# Stm8_Sheet.net
KiCad netlist of a schematic drawn in Altium Designer
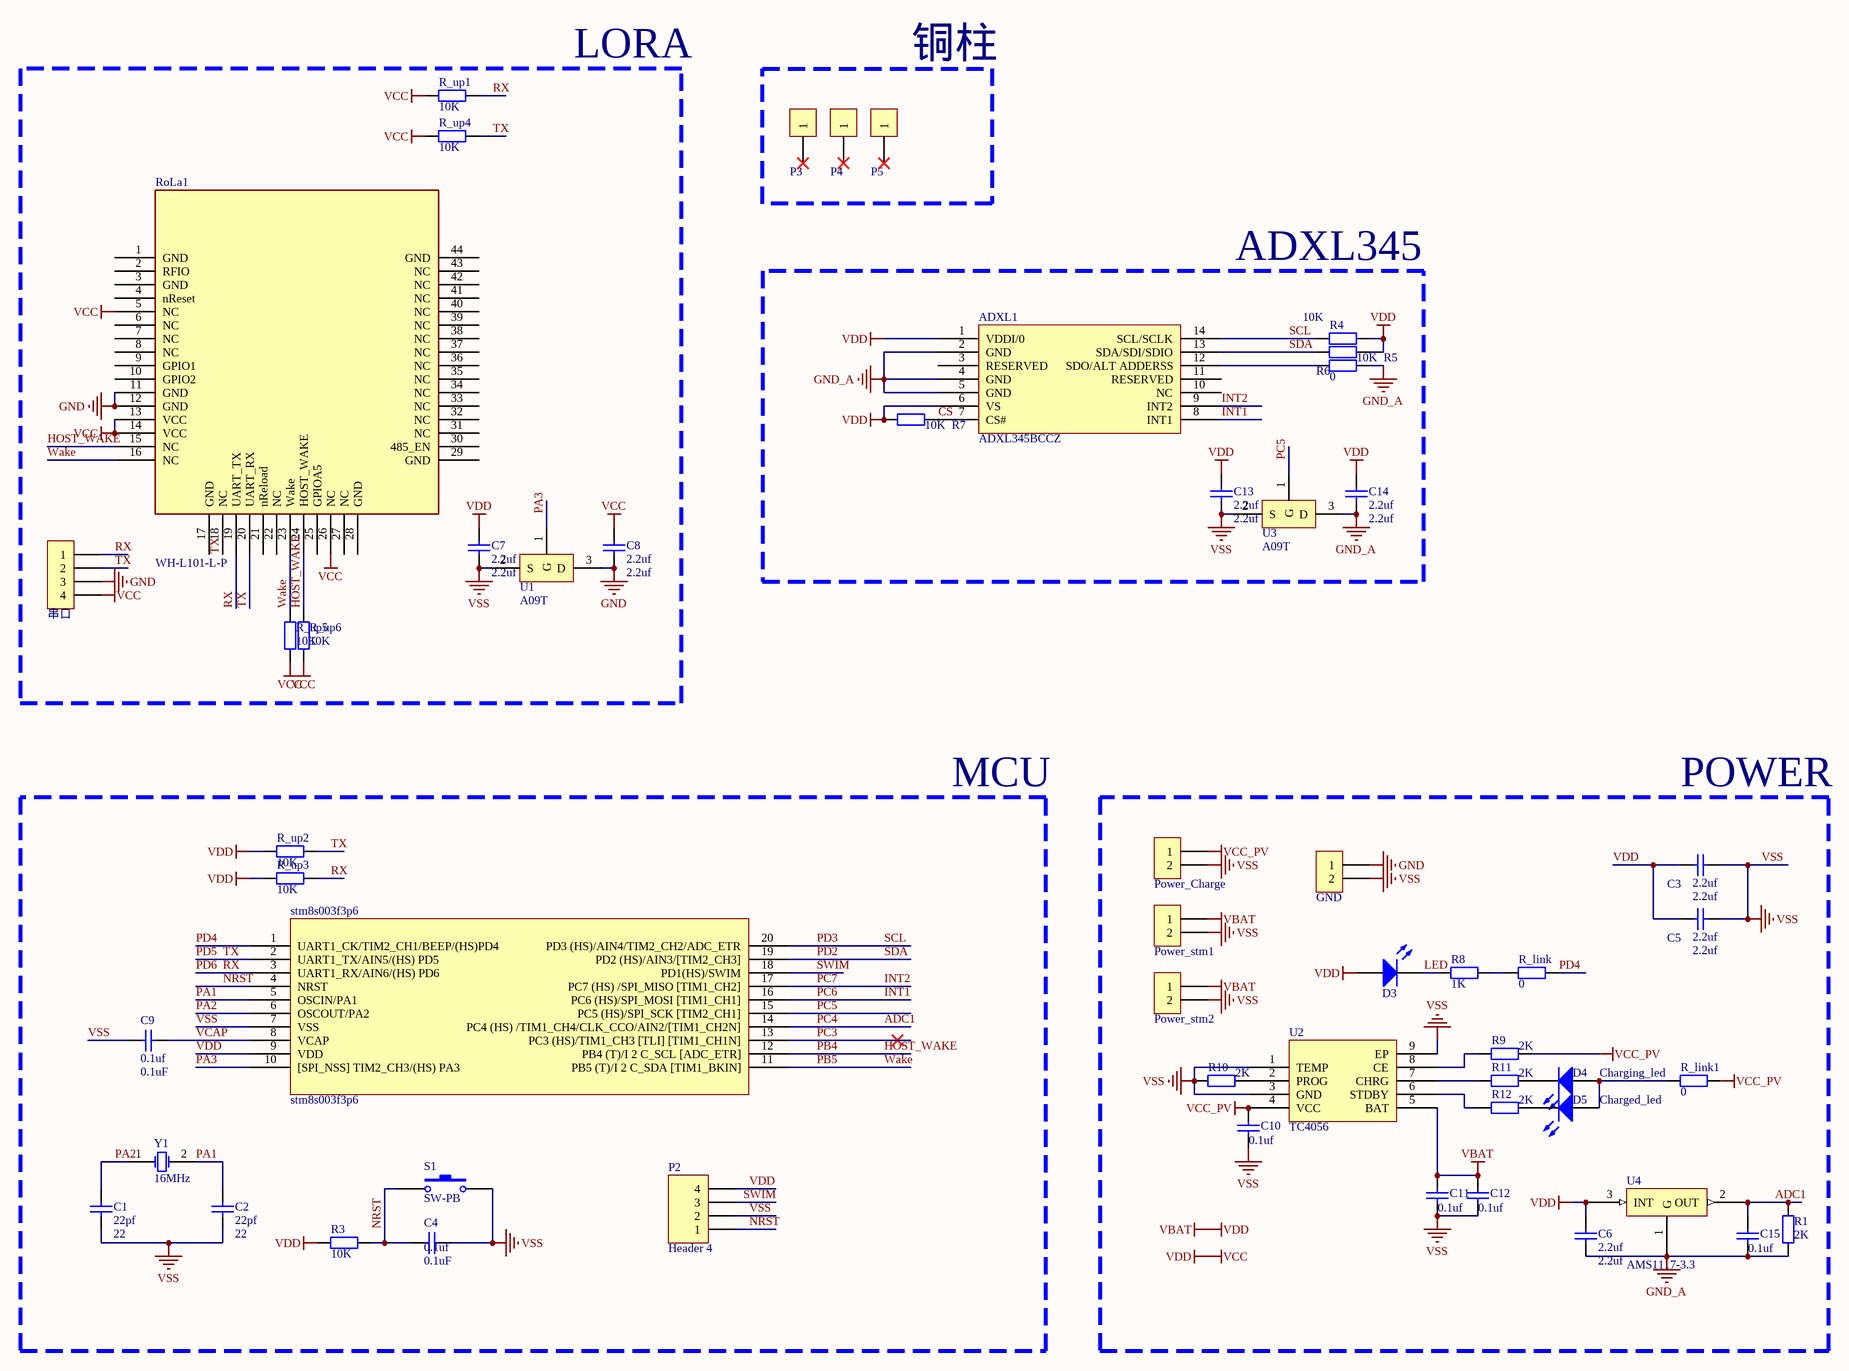
[diagram p0: Stm8_Sheet.SchDoc]

(export (version "E")
  (design (tool "Eeschema 10.0.6"))
  (components
    (comp (ref "ADXL1")
      (value "ADXL345BCCZ")
      (footprint "LGA-14_L5.0-W3.0-P0.80-BL - duplicate")
      (libsource (lib "Stm8_PCB") (part "ADXL345BCCZ"))
    )
    (comp (ref "C1")
      (value "22pf")
      (footprint "Csust_czq6:0603-C")
      (description "Capacitor")
      (fields (field (name "ALTIUM_VALUE") "22") (field (name "PUBLISHER") "Altium Limited"))
      (libsource (lib "PCB_Project") (part "Cap"))
    )
    (comp (ref "C2")
      (value "22pf")
      (footprint "Csust_czq6:0603-C")
      (description "Capacitor")
      (fields (field (name "ALTIUM_VALUE") "22") (field (name "PUBLISHER") "Altium Limited"))
      (libsource (lib "PCB_Project") (part "Cap"))
    )
    (comp (ref "C3")
      (value "2.2uf")
      (footprint "Csust_czq6:0603-C")
      (description "Capacitor")
      (fields (field (name "ALTIUM_VALUE") "2.2uf") (field (name "PUBLISHER") "Altium Limited"))
      (libsource (lib "PCB_Project") (part "Cap"))
    )
    (comp (ref "C4")
      (value "0.1uf")
      (footprint "Csust_czq6:0603-C")
      (description "Capacitor")
      (fields (field (name "ALTIUM_VALUE") "0.1uF") (field (name "PUBLISHER") "Altium Limited"))
      (libsource (lib "Miscellaneous Devices") (part "Cap"))
    )
    (comp (ref "C5")
      (value "2.2uf")
      (footprint "Csust_czq6:0603-C")
      (description "Capacitor")
      (fields (field (name "ALTIUM_VALUE") "2.2uf") (field (name "PUBLISHER") "Altium Limited"))
      (libsource (lib "PCB_Project") (part "Cap"))
    )
    (comp (ref "C6")
      (value "2.2uf")
      (footprint "Csust_czq6:0603-C")
      (description "Capacitor")
      (fields (field (name "ALTIUM_VALUE") "2.2uf") (field (name "PUBLISHER") "Altium Limited"))
      (libsource (lib "PCB_Project") (part "Cap"))
    )
    (comp (ref "C7")
      (value "2.2uf")
      (footprint "Csust_czq6:0603-C")
      (description "Capacitor")
      (fields (field (name "ALTIUM_VALUE") "2.2uf") (field (name "PUBLISHER") "Altium Limited"))
      (libsource (lib "PCB_Project") (part "Cap"))
    )
    (comp (ref "C8")
      (value "2.2uf")
      (footprint "Csust_czq6:0603-C")
      (description "Capacitor")
      (fields (field (name "ALTIUM_VALUE") "2.2uf") (field (name "PUBLISHER") "Altium Limited"))
      (libsource (lib "PCB_Project") (part "Cap"))
    )
    (comp (ref "C9")
      (value "0.1uf")
      (footprint "Csust_czq6:0603-C")
      (description "Capacitor")
      (fields (field (name "ALTIUM_VALUE") "0.1uF") (field (name "PUBLISHER") "Altium Limited"))
      (libsource (lib "Miscellaneous Devices") (part "Cap"))
    )
    (comp (ref "C10")
      (value "0.1uf")
      (footprint "Csust_czq6:0603-C")
      (description "Capacitor")
      (fields (field (name "Comment") "2.2uf") (field (name "PUBLISHER") "Altium Limited"))
      (libsource (lib "PCB_Project") (part "Cap"))
    )
    (comp (ref "C11")
      (value "0.1uf")
      (footprint "Csust_czq6:0603-C")
      (description "Capacitor")
      (fields (field (name "Comment") "2.2uf") (field (name "PUBLISHER") "Altium Limited"))
      (libsource (lib "PCB_Project") (part "Cap"))
    )
    (comp (ref "C12")
      (value "0.1uf")
      (footprint "Csust_czq6:0603-C")
      (description "Capacitor")
      (fields (field (name "Comment") "2.2uf") (field (name "PUBLISHER") "Altium Limited"))
      (libsource (lib "PCB_Project") (part "Cap"))
    )
    (comp (ref "C13")
      (value "2.2uf")
      (footprint "Csust_czq6:0603-C")
      (description "Capacitor")
      (fields (field (name "ALTIUM_VALUE") "2.2uf") (field (name "PUBLISHER") "Altium Limited"))
      (libsource (lib "PCB_Project") (part "Cap"))
    )
    (comp (ref "C14")
      (value "2.2uf")
      (footprint "Csust_czq6:0603-C")
      (description "Capacitor")
      (fields (field (name "ALTIUM_VALUE") "2.2uf") (field (name "PUBLISHER") "Altium Limited"))
      (libsource (lib "PCB_Project") (part "Cap"))
    )
    (comp (ref "C15")
      (value "0.1uf")
      (footprint "Csust_czq6:0603-C")
      (description "Capacitor")
      (fields (field (name "Comment") "2.2uf") (field (name "PUBLISHER") "Altium Limited"))
      (libsource (lib "PCB_Project") (part "Cap"))
    )
    (comp (ref "D3")
      (value "LED0")
      (footprint "Csust_czq6:LED-BLUE-0805")
      (description "发光二极管")
      (fields (field (name "PUBLISHER") "Altium Limited"))
      (libsource (lib "Fszhang") (part "LED0"))
    )
    (comp (ref "D4")
      (value "LED0")
      (footprint "Csust_czq6:LED-BLUE-0805")
      (description "发光二极管")
      (fields (field (name "PUBLISHER") "Altium Limited"))
      (libsource (lib "Fszhang") (part "LED0"))
    )
    (comp (ref "D5")
      (value "LED0")
      (footprint "Csust_czq6:LED-BLUE-0805")
      (description "发光二极管")
      (fields (field (name "PUBLISHER") "Altium Limited"))
      (libsource (lib "Fszhang") (part "LED0"))
    )
    (comp (ref "GND")
      (value "XH接线座-2P")
      (footprint "HDR1X2")
      (libsource (lib "Csust_czq6") (part "XH接线座-2P"))
    )
    (comp (ref "P2")
      (value "Header 4")
      (footprint "HDR1X4")
      (description "Header, 4-Pin")
      (fields (field (name "PUBLISHER") "Altium Limited"))
      (libsource (lib "Miscellaneous Connectors") (part "Header 4"))
    )
    (comp (ref "P3") (value "铜柱孔") (footprint "铜柱孔") (libsource (lib "Csust_czq6") (part "铜柱孔")))
    (comp (ref "P4") (value "铜柱孔") (footprint "铜柱孔") (libsource (lib "Csust_czq6") (part "铜柱孔")))
    (comp (ref "P5") (value "铜柱孔") (footprint "铜柱孔") (libsource (lib "Csust_czq6") (part "铜柱孔")))
    (comp (ref "Power_Charge")
      (value "XH接线座-2P")
      (footprint "XH-2P")
      (libsource (lib "Csust_czq6") (part "XH接线座-2P"))
    )
    (comp (ref "Power_stm1")
      (value "XH接线座-2P")
      (footprint "XH-2P")
      (libsource (lib "Csust_czq6") (part "XH接线座-2P"))
    )
    (comp (ref "Power_stm2")
      (value "XH接线座-2P")
      (footprint "XH-2P")
      (libsource (lib "Csust_czq6") (part "XH接线座-2P"))
    )
    (comp (ref "R1")
      (value "2K")
      (footprint "Csust_czq6:0603-R")
      (description "贴片电阻")
      (fields (field (name "Comment") "1K") (field (name "PUBLISHER") "Altium Limited"))
      (libsource (lib "") (part "Res1_1"))
    )
    (comp (ref "R3")
      (value "10K")
      (footprint "Csust_czq6:0603-R")
      (description "贴片电阻")
      (fields (field (name "PUBLISHER") "Altium Limited"))
      (libsource (lib "Fszhang") (part "Res1"))
    )
    (comp (ref "R4")
      (value "10K")
      (footprint "Csust_czq6:0603-R")
      (description "贴片电阻")
      (fields (field (name "PUBLISHER") "Altium Limited"))
      (libsource (lib "Fszhang") (part "Res1"))
    )
    (comp (ref "R5")
      (value "10K")
      (footprint "Csust_czq6:0603-R")
      (description "贴片电阻")
      (fields (field (name "PUBLISHER") "Altium Limited"))
      (libsource (lib "Fszhang") (part "Res1"))
    )
    (comp (ref "R6")
      (value "0")
      (footprint "Csust_czq6:0603-R")
      (description "贴片电阻")
      (fields (field (name "PUBLISHER") "Altium Limited"))
      (libsource (lib "Fszhang") (part "Res1"))
    )
    (comp (ref "R7")
      (value "10K")
      (footprint "Csust_czq6:0603-R")
      (description "贴片电阻")
      (fields (field (name "PUBLISHER") "Altium Limited"))
      (libsource (lib "Fszhang") (part "Res1"))
    )
    (comp (ref "R8")
      (value "1K")
      (footprint "Csust_czq6:0603-R")
      (description "贴片电阻")
      (fields (field (name "PUBLISHER") "Altium Limited"))
      (libsource (lib "Fszhang") (part "Res1"))
    )
    (comp (ref "R9")
      (value "2K")
      (footprint "Csust_czq6:0603-R")
      (description "贴片电阻")
      (fields (field (name "Comment") "1K") (field (name "PUBLISHER") "Altium Limited"))
      (libsource (lib "Fszhang") (part "Res1"))
    )
    (comp (ref "R10")
      (value "2K")
      (footprint "Csust_czq6:0603-R")
      (description "贴片电阻")
      (fields (field (name "Comment") "1K") (field (name "PUBLISHER") "Altium Limited"))
      (libsource (lib "Fszhang") (part "Res1"))
    )
    (comp (ref "R11")
      (value "2K")
      (footprint "Csust_czq6:0603-R")
      (description "贴片电阻")
      (fields (field (name "Comment") "1K") (field (name "PUBLISHER") "Altium Limited"))
      (libsource (lib "Fszhang") (part "Res1"))
    )
    (comp (ref "R12")
      (value "2K")
      (footprint "Csust_czq6:0603-R")
      (description "贴片电阻")
      (fields (field (name "Comment") "1K") (field (name "PUBLISHER") "Altium Limited"))
      (libsource (lib "Fszhang") (part "Res1"))
    )
    (comp (ref "RoLa1")
      (value "WH-L101-L-P")
      (footprint "WH-L101-L-P")
      (libsource (lib "steven") (part "WH-L101-L-P"))
    )
    (comp (ref "R_link")
      (value "0")
      (footprint "0402")
      (description "贴片电阻")
      (fields (field (name "Comment") "1K") (field (name "PUBLISHER") "Altium Limited"))
      (libsource (lib "Fszhang") (part "Res1"))
    )
    (comp (ref "R_link1")
      (value "0")
      (footprint "0402")
      (description "贴片电阻")
      (fields (field (name "Comment") "1K") (field (name "PUBLISHER") "Altium Limited"))
      (libsource (lib "Fszhang") (part "Res1"))
    )
    (comp (ref "R_up1")
      (value "10K")
      (footprint "Csust_czq6:0603-R")
      (description "贴片电阻")
      (fields (field (name "PUBLISHER") "Altium Limited"))
      (libsource (lib "Fszhang") (part "Res1"))
    )
    (comp (ref "R_up2")
      (value "10K")
      (footprint "Csust_czq6:0603-R")
      (description "贴片电阻")
      (fields (field (name "PUBLISHER") "Altium Limited"))
      (libsource (lib "Fszhang") (part "Res1"))
    )
    (comp (ref "R_up3")
      (value "10K")
      (footprint "Csust_czq6:0603-R")
      (description "贴片电阻")
      (fields (field (name "PUBLISHER") "Altium Limited"))
      (libsource (lib "Fszhang") (part "Res1"))
    )
    (comp (ref "R_up4")
      (value "10K")
      (footprint "Csust_czq6:0603-R")
      (description "贴片电阻")
      (fields (field (name "PUBLISHER") "Altium Limited"))
      (libsource (lib "Fszhang") (part "Res1"))
    )
    (comp (ref "R_up5")
      (value "10K")
      (footprint "Csust_czq6:0603-R")
      (description "贴片电阻")
      (fields (field (name "PUBLISHER") "Altium Limited"))
      (libsource (lib "") (part "Res1_1"))
    )
    (comp (ref "R_up6")
      (value "10K")
      (footprint "Csust_czq6:0603-R")
      (description "贴片电阻")
      (fields (field (name "PUBLISHER") "Altium Limited"))
      (libsource (lib "") (part "Res1_1"))
    )
    (comp (ref "S1")
      (value "SW-PB")
      (footprint "Csust_czq6:按键(贴片)")
      (description "微动开关")
      (fields (field (name "PUBLISHER") "Altium Limited"))
      (libsource (lib "Fszhang") (part "SW-PB"))
    )
    (comp (ref "stm8s003f3p6")
      (value "stm8s003f3p6")
      (footprint "TSSOP20")
      (libsource (lib "steven") (part "stm8s003f3p6"))
    )
    (comp (ref "U1") (value "A09T") (footprint "SOT23") (libsource (lib "steven") (part "A09T")))
    (comp (ref "U2")
      (value "TC4056")
      (footprint "SOP-8_L4.9-W3.9-P1.27-LS6.0-BL-EP")
      (description "TC4056电源模块")
      (libsource (lib "steven") (part "TC4056"))
    )
    (comp (ref "U3") (value "A09T") (footprint "SOT23") (libsource (lib "steven") (part "A09T")))
    (comp (ref "U4")
      (value "AMS1117-3.3")
      (footprint "SOT-223")
      (libsource (lib "steven") (part "AMS1117-3.3"))
    )
    (comp (ref "Y1")
      (value "16MHz")
      (footprint "OSC-SMD_L5.0-W3.2 - duplicate")
      (description "Crystal Oscillator")
      (fields (field (name "PUBLISHER") "Altium Limited"))
      (libsource (lib "steven") (part "XTAL_1"))
    )
    (comp (ref "串口") (value "XH接线座-4P") (footprint "HDR1X4") (libsource (lib "Csust_czq6") (part "XH接线座-4P")))
  )
  (nets
    (net (code "1") (name "/ADC1") (class "Default")
      (node (ref "C15") (pin "1") (pinfunction "1_1") (pintype "passive"))
      (node (ref "R1") (pin "1") (pinfunction "1_1") (pintype "passive"))
      (node (ref "U4") (pin "2") (pinfunction "OUT_2") (pintype "output"))
      (node (ref "stm8s003f3p6") (pin "14") (pinfunction "PC4_(HS)_/TIM1_CH4/CLK_CCO/AIN2/[TIM1_CH2N]_14") (pintype "passive"))
    )
    (net (code "2") (name "/CS") (class "Default")
      (node (ref "ADXL1") (pin "7") (pinfunction "CS#_7") (pintype "passive"))
      (node (ref "R7") (pin "1") (pinfunction "1_1") (pintype "passive"))
    )
    (net (code "3") (name "/HOST_WAKE") (class "Default")
      (node (ref "R_up6") (pin "1") (pinfunction "1_1") (pintype "passive"))
      (node (ref "RoLa1") (pin "15") (pinfunction "NC_15") (pintype "passive"))
      (node (ref "RoLa1") (pin "24") (pinfunction "HOST_WAKE_24") (pintype "passive"))
      (node (ref "stm8s003f3p6") (pin "12") (pinfunction "PB4_(T)/I_2_C_SCL_[ADC_ETR]_12") (pintype "passive"))
    )
    (net (code "4") (name "/INT1") (class "Default")
      (node (ref "ADXL1") (pin "8") (pinfunction "INT1_8") (pintype "passive"))
      (node (ref "stm8s003f3p6") (pin "16") (pinfunction "PC6_(HS)/SPI_MOSI_[TIM1_CH1]_16") (pintype "passive"))
    )
    (net (code "5") (name "/INT2") (class "Default")
      (node (ref "ADXL1") (pin "9") (pinfunction "INT2_9") (pintype "passive"))
      (node (ref "stm8s003f3p6") (pin "17") (pinfunction "PC7_(HS)_/SPI_MISO_[TIM1_CH2]_17") (pintype "passive"))
    )
    (net (code "6") (name "/LED") (class "Default")
      (node (ref "D3") (pin "2") (pinfunction "K_2") (pintype "passive"))
      (node (ref "R8") (pin "2") (pinfunction "2_2") (pintype "passive"))
    )
    (net (code "7") (name "/NRST") (class "Default")
      (node (ref "C4") (pin "2") (pinfunction "2_2") (pintype "passive"))
      (node (ref "P2") (pin "1") (pinfunction "1_1") (pintype "passive"))
      (node (ref "R3") (pin "1") (pinfunction "1_1") (pintype "passive"))
      (node (ref "S1") (pin "1") (pinfunction "1_1") (pintype "passive"))
      (node (ref "stm8s003f3p6") (pin "4") (pinfunction "NRST_4") (pintype "passive"))
    )
    (net (code "8") (name "/PA1") (class "Default")
      (node (ref "C2") (pin "2") (pinfunction "2_2") (pintype "passive"))
      (node (ref "Y1") (pin "2") (pinfunction "OSC2_2") (pintype "passive"))
      (node (ref "stm8s003f3p6") (pin "5") (pinfunction "OSCIN/PA1_5") (pintype "passive"))
    )
    (net (code "9") (name "/PA2") (class "Default")
      (node (ref "C1") (pin "2") (pinfunction "2_2") (pintype "passive"))
      (node (ref "Y1") (pin "1") (pinfunction "OSC1_1") (pintype "passive"))
      (node (ref "stm8s003f3p6") (pin "6") (pinfunction "OSCOUT/PA2_6") (pintype "passive"))
    )
    (net (code "10") (name "/PA3") (class "Default")
      (node (ref "U1") (pin "1") (pinfunction "G_1") (pintype "passive"))
      (node (ref "stm8s003f3p6") (pin "10") (pinfunction "[SPI_NSS]_TIM2_CH3/(HS)_PA3_10") (pintype "passive"))
    )
    (net (code "11") (name "/PB5") (class "Default")
      (node (ref "R_up5") (pin "1") (pinfunction "1_1") (pintype "passive"))
      (node (ref "RoLa1") (pin "16") (pinfunction "NC_16") (pintype "passive"))
      (node (ref "RoLa1") (pin "23") (pinfunction "Wake_23") (pintype "passive"))
      (node (ref "stm8s003f3p6") (pin "11") (pinfunction "PB5_(T)/I_2_C_SDA_[TIM1_BKIN]_11") (pintype "passive"))
    )
    (net (code "12") (name "/PC3") (class "Default")
      (node (ref "stm8s003f3p6") (pin "13") (pinfunction "PC3_(HS)/TIM1_CH3_[TLI]_[TIM1_CH1N]_13") (pintype "passive"))
    )
    (net (code "13") (name "/PC5") (class "Default")
      (node (ref "U3") (pin "1") (pinfunction "G_1") (pintype "passive"))
      (node (ref "stm8s003f3p6") (pin "15") (pinfunction "PC5_(HS)/SPI_SCK_[TIM2_CH1]_15") (pintype "passive"))
    )
    (net (code "14") (name "/PD2") (class "Default")
      (node (ref "ADXL1") (pin "13") (pinfunction "SDA/SDI/SDIO_13") (pintype "passive"))
      (node (ref "R5") (pin "2") (pinfunction "2_2") (pintype "passive"))
      (node (ref "stm8s003f3p6") (pin "19") (pinfunction "PD2_(HS)/AIN3/[TIM2_CH3]_19") (pintype "passive"))
    )
    (net (code "15") (name "/PD3") (class "Default")
      (node (ref "ADXL1") (pin "14") (pinfunction "SCL/SCLK_14") (pintype "passive"))
      (node (ref "R4") (pin "2") (pinfunction "2_2") (pintype "passive"))
      (node (ref "stm8s003f3p6") (pin "20") (pinfunction "PD3_(HS)/AIN4/TIM2_CH2/ADC_ETR_20") (pintype "passive"))
    )
    (net (code "16") (name "/PD4") (class "Default")
      (node (ref "R_link") (pin "1") (pinfunction "1_1") (pintype "passive"))
      (node (ref "stm8s003f3p6") (pin "1") (pinfunction "UART1_CK/TIM2_CH1/BEEP/(HS)PD4_1") (pintype "passive"))
    )
    (net (code "17") (name "/PD5") (class "Default")
      (node (ref "R_up2") (pin "1") (pinfunction "1_1") (pintype "passive"))
      (node (ref "R_up4") (pin "1") (pinfunction "1_1") (pintype "passive"))
      (node (ref "RoLa1") (pin "18") (pinfunction "NC_18") (pintype "passive"))
      (node (ref "RoLa1") (pin "20") (pinfunction "UART_RX_20") (pintype "passive"))
      (node (ref "stm8s003f3p6") (pin "2") (pinfunction "UART1_TX/AIN5/(HS)_PD5_2") (pintype "passive"))
      (node (ref "串口") (pin "2") (pinfunction "2_2") (pintype "passive"))
    )
    (net (code "18") (name "/PD6") (class "Default")
      (node (ref "R_up1") (pin "1") (pinfunction "1_1") (pintype "passive"))
      (node (ref "R_up3") (pin "1") (pinfunction "1_1") (pintype "passive"))
      (node (ref "RoLa1") (pin "19") (pinfunction "UART_TX_19") (pintype "passive"))
      (node (ref "stm8s003f3p6") (pin "3") (pinfunction "UART1_RX/AIN6/(HS)_PD6_3") (pintype "passive"))
      (node (ref "串口") (pin "1") (pinfunction "1_1") (pintype "passive"))
    )
    (net (code "19") (name "/SWIM") (class "Default")
      (node (ref "P2") (pin "3") (pinfunction "3_3") (pintype "passive"))
      (node (ref "stm8s003f3p6") (pin "18") (pinfunction "PD1(HS)/SWIM_18") (pintype "passive"))
    )
    (net (code "20") (name "/VCAP") (class "Default")
      (node (ref "C9") (pin "1") (pinfunction "1_1") (pintype "passive"))
      (node (ref "stm8s003f3p6") (pin "8") (pinfunction "VCAP_8") (pintype "passive"))
    )
    (net (code "21") (name "GND") (class "Default")
      (node (ref "C8") (pin "2") (pinfunction "2_2") (pintype "passive"))
      (node (ref "GND") (pin "1") (pinfunction "1_1") (pintype "passive"))
      (node (ref "RoLa1") (pin "11") (pinfunction "GND_11") (pintype "passive"))
      (node (ref "RoLa1") (pin "12") (pinfunction "GND_12") (pintype "passive"))
      (node (ref "U1") (pin "3") (pinfunction "D_3") (pintype "passive"))
      (node (ref "串口") (pin "3") (pinfunction "3_3") (pintype "passive"))
    )
    (net (code "22") (name "GND_A") (class "Default")
      (node (ref "ADXL1") (pin "2") (pinfunction "GND_2") (pintype "passive"))
      (node (ref "ADXL1") (pin "4") (pinfunction "GND_4") (pintype "passive"))
      (node (ref "ADXL1") (pin "5") (pinfunction "GND_5") (pintype "passive"))
      (node (ref "C14") (pin "2") (pinfunction "2_2") (pintype "passive"))
      (node (ref "C15") (pin "2") (pinfunction "2_2") (pintype "passive"))
      (node (ref "C6") (pin "2") (pinfunction "2_2") (pintype "passive"))
      (node (ref "R1") (pin "2") (pinfunction "2_2") (pintype "passive"))
      (node (ref "R6") (pin "1") (pinfunction "1_1") (pintype "passive"))
      (node (ref "U3") (pin "3") (pinfunction "D_3") (pintype "passive"))
      (node (ref "U4") (pin "1") (pinfunction "G_1") (pintype "passive"))
    )
    (net (code "23") (name "Net-(ADXL1-SDO{slash}ALT_ADDERSS)") (class "Default")
      (node (ref "ADXL1") (pin "12") (pinfunction "SDO/ALT_ADDERSS_12") (pintype "passive"))
      (node (ref "R6") (pin "2") (pinfunction "2_2") (pintype "passive"))
    )
    (net (code "24") (name "Net-(D4-A)") (class "Default")
      (node (ref "D4") (pin "1") (pinfunction "A_1") (pintype "passive"))
      (node (ref "D5") (pin "1") (pinfunction "A_1") (pintype "passive"))
      (node (ref "R_link1") (pin "2") (pinfunction "2_2") (pintype "passive"))
    )
    (net (code "25") (name "Net-(D4-K)") (class "Default")
      (node (ref "D4") (pin "2") (pinfunction "K_2") (pintype "passive"))
      (node (ref "R11") (pin "1") (pinfunction "1_1") (pintype "passive"))
    )
    (net (code "26") (name "Net-(D5-K)") (class "Default")
      (node (ref "D5") (pin "2") (pinfunction "K_2") (pintype "passive"))
      (node (ref "R12") (pin "1") (pinfunction "1_1") (pintype "passive"))
    )
    (net (code "27") (name "Net-(R8-Pad1)") (class "Default")
      (node (ref "R8") (pin "1") (pinfunction "1_1") (pintype "passive"))
      (node (ref "R_link") (pin "2") (pinfunction "2_2") (pintype "passive"))
    )
    (net (code "28") (name "Net-(U2-CE)") (class "Default")
      (node (ref "R9") (pin "2") (pinfunction "2_2") (pintype "passive"))
      (node (ref "U2") (pin "8") (pinfunction "CE_8") (pintype "passive"))
    )
    (net (code "29") (name "Net-(U2-CHRG)") (class "Default")
      (node (ref "R11") (pin "2") (pinfunction "2_2") (pintype "passive"))
      (node (ref "U2") (pin "7") (pinfunction "CHRG_7") (pintype "passive"))
    )
    (net (code "30") (name "Net-(U2-PROG)") (class "Default")
      (node (ref "R10") (pin "1") (pinfunction "1_1") (pintype "passive"))
      (node (ref "U2") (pin "2") (pinfunction "PROG_2") (pintype "passive"))
    )
    (net (code "31") (name "Net-(U2-STDBY)") (class "Default")
      (node (ref "R12") (pin "2") (pinfunction "2_2") (pintype "passive"))
      (node (ref "U2") (pin "6") (pinfunction "STDBY_6") (pintype "passive"))
    )
    (net (code "32") (name "VBAT") (class "Default")
      (node (ref "ADXL1") (pin "1") (pinfunction "VDDI/0_1") (pintype "passive"))
      (node (ref "ADXL1") (pin "6") (pinfunction "VS_6") (pintype "passive"))
      (node (ref "C11") (pin "1") (pinfunction "1_1") (pintype "passive"))
      (node (ref "C12") (pin "1") (pinfunction "1_1") (pintype "passive"))
      (node (ref "C13") (pin "1") (pinfunction "1_1") (pintype "passive"))
      (node (ref "C14") (pin "1") (pinfunction "1_1") (pintype "passive"))
      (node (ref "C3") (pin "2") (pinfunction "2_2") (pintype "passive"))
      (node (ref "C5") (pin "2") (pinfunction "2_2") (pintype "passive"))
      (node (ref "C6") (pin "1") (pinfunction "1_1") (pintype "passive"))
      (node (ref "C7") (pin "1") (pinfunction "1_1") (pintype "passive"))
      (node (ref "C8") (pin "1") (pinfunction "1_1") (pintype "passive"))
      (node (ref "D3") (pin "1") (pinfunction "A_1") (pintype "passive"))
      (node (ref "P2") (pin "4") (pinfunction "4_4") (pintype "passive"))
      (node (ref "Power_stm1") (pin "1") (pinfunction "1_1") (pintype "passive"))
      (node (ref "Power_stm2") (pin "1") (pinfunction "1_1") (pintype "passive"))
      (node (ref "R3") (pin "2") (pinfunction "2_2") (pintype "passive"))
      (node (ref "R4") (pin "1") (pinfunction "1_1") (pintype "passive"))
      (node (ref "R5") (pin "1") (pinfunction "1_1") (pintype "passive"))
      (node (ref "R7") (pin "2") (pinfunction "2_2") (pintype "passive"))
      (node (ref "R_up1") (pin "2") (pinfunction "2_2") (pintype "passive"))
      (node (ref "R_up2") (pin "2") (pinfunction "2_2") (pintype "passive"))
      (node (ref "R_up3") (pin "2") (pinfunction "2_2") (pintype "passive"))
      (node (ref "R_up4") (pin "2") (pinfunction "2_2") (pintype "passive"))
      (node (ref "R_up5") (pin "2") (pinfunction "2_2") (pintype "passive"))
      (node (ref "R_up6") (pin "2") (pinfunction "2_2") (pintype "passive"))
      (node (ref "RoLa1") (pin "13") (pinfunction "VCC_13") (pintype "passive"))
      (node (ref "RoLa1") (pin "14") (pinfunction "VCC_14") (pintype "passive"))
      (node (ref "RoLa1") (pin "26") (pinfunction "NC_26") (pintype "passive"))
      (node (ref "RoLa1") (pin "5") (pinfunction "NC_5") (pintype "passive"))
      (node (ref "U2") (pin "5") (pinfunction "BAT_5") (pintype "passive"))
      (node (ref "U4") (pin "3") (pinfunction "INT_3") (pintype "input"))
      (node (ref "stm8s003f3p6") (pin "9") (pinfunction "VDD_9") (pintype "passive"))
      (node (ref "串口") (pin "4") (pinfunction "4_4") (pintype "passive"))
    )
    (net (code "33") (name "VCC_PV") (class "Default")
      (node (ref "C10") (pin "1") (pinfunction "1_1") (pintype "passive"))
      (node (ref "Power_Charge") (pin "1") (pinfunction "1_1") (pintype "passive"))
      (node (ref "R9") (pin "1") (pinfunction "1_1") (pintype "passive"))
      (node (ref "R_link1") (pin "1") (pinfunction "1_1") (pintype "passive"))
      (node (ref "U2") (pin "4") (pinfunction "VCC_4") (pintype "passive"))
    )
    (net (code "34") (name "VSS") (class "Default")
      (node (ref "C1") (pin "1") (pinfunction "1_1") (pintype "passive"))
      (node (ref "C10") (pin "2") (pinfunction "2_2") (pintype "passive"))
      (node (ref "C11") (pin "2") (pinfunction "2_2") (pintype "passive"))
      (node (ref "C12") (pin "2") (pinfunction "2_2") (pintype "passive"))
      (node (ref "C13") (pin "2") (pinfunction "2_2") (pintype "passive"))
      (node (ref "C2") (pin "1") (pinfunction "1_1") (pintype "passive"))
      (node (ref "C3") (pin "1") (pinfunction "1_1") (pintype "passive"))
      (node (ref "C4") (pin "1") (pinfunction "1_1") (pintype "passive"))
      (node (ref "C5") (pin "1") (pinfunction "1_1") (pintype "passive"))
      (node (ref "C7") (pin "2") (pinfunction "2_2") (pintype "passive"))
      (node (ref "C9") (pin "2") (pinfunction "2_2") (pintype "passive"))
      (node (ref "GND") (pin "2") (pinfunction "2_2") (pintype "passive"))
      (node (ref "P2") (pin "2") (pinfunction "2_2") (pintype "passive"))
      (node (ref "Power_Charge") (pin "2") (pinfunction "2_2") (pintype "passive"))
      (node (ref "Power_stm1") (pin "2") (pinfunction "2_2") (pintype "passive"))
      (node (ref "Power_stm2") (pin "2") (pinfunction "2_2") (pintype "passive"))
      (node (ref "R10") (pin "2") (pinfunction "2_2") (pintype "passive"))
      (node (ref "S1") (pin "2") (pinfunction "2_2") (pintype "passive"))
      (node (ref "U1") (pin "2") (pinfunction "S_2") (pintype "passive"))
      (node (ref "U2") (pin "1") (pinfunction "TEMP_1") (pintype "passive"))
      (node (ref "U2") (pin "3") (pinfunction "GND_3") (pintype "passive"))
      (node (ref "U2") (pin "9") (pinfunction "EP_9") (pintype "passive"))
      (node (ref "U3") (pin "2") (pinfunction "S_2") (pintype "passive"))
      (node (ref "stm8s003f3p6") (pin "7") (pinfunction "VSS_7") (pintype "passive"))
    )
    (net (code "35") (name "unconnected-(ADXL1-NC-Pad10)") (class "Default")
      (node (ref "ADXL1") (pin "10") (pinfunction "NC_10") (pintype "passive"))
    )
    (net (code "36") (name "unconnected-(ADXL1-RESERVED-Pad3)") (class "Default")
      (node (ref "ADXL1") (pin "3") (pinfunction "RESERVED_3") (pintype "passive"))
    )
    (net (code "37") (name "unconnected-(ADXL1-RESERVED-Pad11)") (class "Default")
      (node (ref "ADXL1") (pin "11") (pinfunction "RESERVED_11") (pintype "passive"))
    )
    (net (code "38") (name "unconnected-(P3-Pad1)") (class "Default")
      (node (ref "P3") (pin "1") (pinfunction "1_1") (pintype "passive+no_connect"))
    )
    (net (code "39") (name "unconnected-(P4-Pad1)") (class "Default")
      (node (ref "P4") (pin "1") (pinfunction "1_1") (pintype "passive+no_connect"))
    )
    (net (code "40") (name "unconnected-(P5-Pad1)") (class "Default")
      (node (ref "P5") (pin "1") (pinfunction "1_1") (pintype "passive+no_connect"))
    )
    (net (code "41") (name "unconnected-(RoLa1-485_EN-Pad30)") (class "Default")
      (node (ref "RoLa1") (pin "30") (pinfunction "485_EN_30") (pintype "passive"))
    )
    (net (code "42") (name "unconnected-(RoLa1-GND-Pad1)") (class "Default")
      (node (ref "RoLa1") (pin "1") (pinfunction "GND_1") (pintype "passive"))
    )
    (net (code "43") (name "unconnected-(RoLa1-GND-Pad3)") (class "Default")
      (node (ref "RoLa1") (pin "3") (pinfunction "GND_3") (pintype "passive"))
    )
    (net (code "44") (name "unconnected-(RoLa1-GND-Pad17)") (class "Default")
      (node (ref "RoLa1") (pin "17") (pinfunction "GND_17") (pintype "passive"))
    )
    (net (code "45") (name "unconnected-(RoLa1-GND-Pad28)") (class "Default")
      (node (ref "RoLa1") (pin "28") (pinfunction "GND_28") (pintype "passive"))
    )
    (net (code "46") (name "unconnected-(RoLa1-GND-Pad29)") (class "Default")
      (node (ref "RoLa1") (pin "29") (pinfunction "GND_29") (pintype "passive"))
    )
    (net (code "47") (name "unconnected-(RoLa1-GND-Pad44)") (class "Default")
      (node (ref "RoLa1") (pin "44") (pinfunction "GND_44") (pintype "passive"))
    )
    (net (code "48") (name "unconnected-(RoLa1-GPIO1-Pad9)") (class "Default")
      (node (ref "RoLa1") (pin "9") (pinfunction "GPIO1_9") (pintype "passive"))
    )
    (net (code "49") (name "unconnected-(RoLa1-GPIO2-Pad10)") (class "Default")
      (node (ref "RoLa1") (pin "10") (pinfunction "GPIO2_10") (pintype "passive"))
    )
    (net (code "50") (name "unconnected-(RoLa1-GPIOA5-Pad25)") (class "Default")
      (node (ref "RoLa1") (pin "25") (pinfunction "GPIOA5_25") (pintype "passive"))
    )
    (net (code "51") (name "unconnected-(RoLa1-NC-Pad6)") (class "Default")
      (node (ref "RoLa1") (pin "6") (pinfunction "NC_6") (pintype "passive"))
    )
    (net (code "52") (name "unconnected-(RoLa1-NC-Pad7)") (class "Default")
      (node (ref "RoLa1") (pin "7") (pinfunction "NC_7") (pintype "passive"))
    )
    (net (code "53") (name "unconnected-(RoLa1-NC-Pad8)") (class "Default")
      (node (ref "RoLa1") (pin "8") (pinfunction "NC_8") (pintype "passive"))
    )
    (net (code "54") (name "unconnected-(RoLa1-NC-Pad22)") (class "Default")
      (node (ref "RoLa1") (pin "22") (pinfunction "NC_22") (pintype "passive"))
    )
    (net (code "55") (name "unconnected-(RoLa1-NC-Pad27)") (class "Default")
      (node (ref "RoLa1") (pin "27") (pinfunction "NC_27") (pintype "passive"))
    )
    (net (code "56") (name "unconnected-(RoLa1-NC-Pad31)") (class "Default")
      (node (ref "RoLa1") (pin "31") (pinfunction "NC_31") (pintype "passive"))
    )
    (net (code "57") (name "unconnected-(RoLa1-NC-Pad32)") (class "Default")
      (node (ref "RoLa1") (pin "32") (pinfunction "NC_32") (pintype "passive"))
    )
    (net (code "58") (name "unconnected-(RoLa1-NC-Pad33)") (class "Default")
      (node (ref "RoLa1") (pin "33") (pinfunction "NC_33") (pintype "passive"))
    )
    (net (code "59") (name "unconnected-(RoLa1-NC-Pad34)") (class "Default")
      (node (ref "RoLa1") (pin "34") (pinfunction "NC_34") (pintype "passive"))
    )
    (net (code "60") (name "unconnected-(RoLa1-NC-Pad35)") (class "Default")
      (node (ref "RoLa1") (pin "35") (pinfunction "NC_35") (pintype "passive"))
    )
    (net (code "61") (name "unconnected-(RoLa1-NC-Pad36)") (class "Default")
      (node (ref "RoLa1") (pin "36") (pinfunction "NC_36") (pintype "passive"))
    )
    (net (code "62") (name "unconnected-(RoLa1-NC-Pad37)") (class "Default")
      (node (ref "RoLa1") (pin "37") (pinfunction "NC_37") (pintype "passive"))
    )
    (net (code "63") (name "unconnected-(RoLa1-NC-Pad38)") (class "Default")
      (node (ref "RoLa1") (pin "38") (pinfunction "NC_38") (pintype "passive"))
    )
    (net (code "64") (name "unconnected-(RoLa1-NC-Pad39)") (class "Default")
      (node (ref "RoLa1") (pin "39") (pinfunction "NC_39") (pintype "passive"))
    )
    (net (code "65") (name "unconnected-(RoLa1-NC-Pad40)") (class "Default")
      (node (ref "RoLa1") (pin "40") (pinfunction "NC_40") (pintype "passive"))
    )
    (net (code "66") (name "unconnected-(RoLa1-NC-Pad41)") (class "Default")
      (node (ref "RoLa1") (pin "41") (pinfunction "NC_41") (pintype "passive"))
    )
    (net (code "67") (name "unconnected-(RoLa1-NC-Pad42)") (class "Default")
      (node (ref "RoLa1") (pin "42") (pinfunction "NC_42") (pintype "passive"))
    )
    (net (code "68") (name "unconnected-(RoLa1-NC-Pad43)") (class "Default")
      (node (ref "RoLa1") (pin "43") (pinfunction "NC_43") (pintype "passive"))
    )
    (net (code "69") (name "unconnected-(RoLa1-RFIO-Pad2)") (class "Default")
      (node (ref "RoLa1") (pin "2") (pinfunction "RFIO_2") (pintype "passive"))
    )
    (net (code "70") (name "unconnected-(RoLa1-nReload-Pad21)") (class "Default")
      (node (ref "RoLa1") (pin "21") (pinfunction "nReload_21") (pintype "passive"))
    )
    (net (code "71") (name "unconnected-(RoLa1-nReset-Pad4)") (class "Default")
      (node (ref "RoLa1") (pin "4") (pinfunction "nReset_4") (pintype "passive"))
    )
  )
)
